# 05-5V_Monitor.net
KiCad netlist of a schematic drawn in Altium Designer
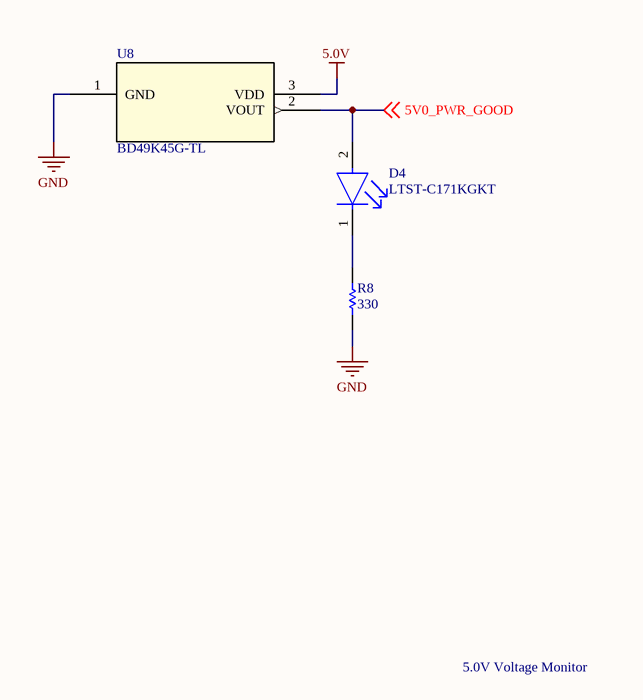
[diagram p0: 05-5V_Monitor.SchDoc]

(export (version "E")
  (design (tool "Eeschema 10.0.6"))
  (components
    (comp (ref "D4")
      (value "LTST-C171KGKT")
      (footprint "FP-LTST-C171KGKT-MFG")
      (description "LED GREEN CLEAR SMD")
      (libsource (lib "Altium Content Vault") (part "8706943c75ba83719d021d2fdc84c58"))
    )
    (comp (ref "R8")
      (value "330")
      (footprint "RES_0805")
      (description "RES 330 OHM 1% 1/8W 0805")
      (fields (field (name "TOLERANCE") "1%"))
      (libsource (lib "team6") (part "RES_0805_R_330.00"))
    )
    (comp (ref "U8")
      (value "BD49K45G-TL")
      (footprint "SSOP3_ROM")
      (description "No Description Available")
      (fields (field (name "COPYRIGHT") "Copyright (C) 2022 Ultra Librarian. All rights reserved."))
      (libsource (lib "team6") (part "BD49K45G-TL"))
    )
  )
  (nets
    (net (code "1") (name "5.0V") (class "Default")
      (node (ref "U8") (pin "3") (pinfunction "VDD_3") (pintype "power_in"))
    )
    (net (code "2") (name "5V0_PWR_GOOD") (class "Default")
      (node (ref "D4") (pin "2") (pinfunction "A_2") (pintype "passive"))
      (node (ref "U8") (pin "2") (pinfunction "VOUT_2") (pintype "output"))
    )
    (net (code "3") (name "GND") (class "Default")
      (node (ref "R8") (pin "1") (pinfunction "1_1") (pintype "passive"))
      (node (ref "U8") (pin "1") (pinfunction "GND_1") (pintype "passive"))
    )
    (net (code "4") (name "Net-(D4-C)") (class "Default")
      (node (ref "D4") (pin "1") (pinfunction "C_1") (pintype "passive"))
      (node (ref "R8") (pin "2") (pinfunction "2_2") (pintype "passive"))
    )
  )
)
